# INS_CAN.net
KiCad netlist of a schematic drawn in Altium Designer
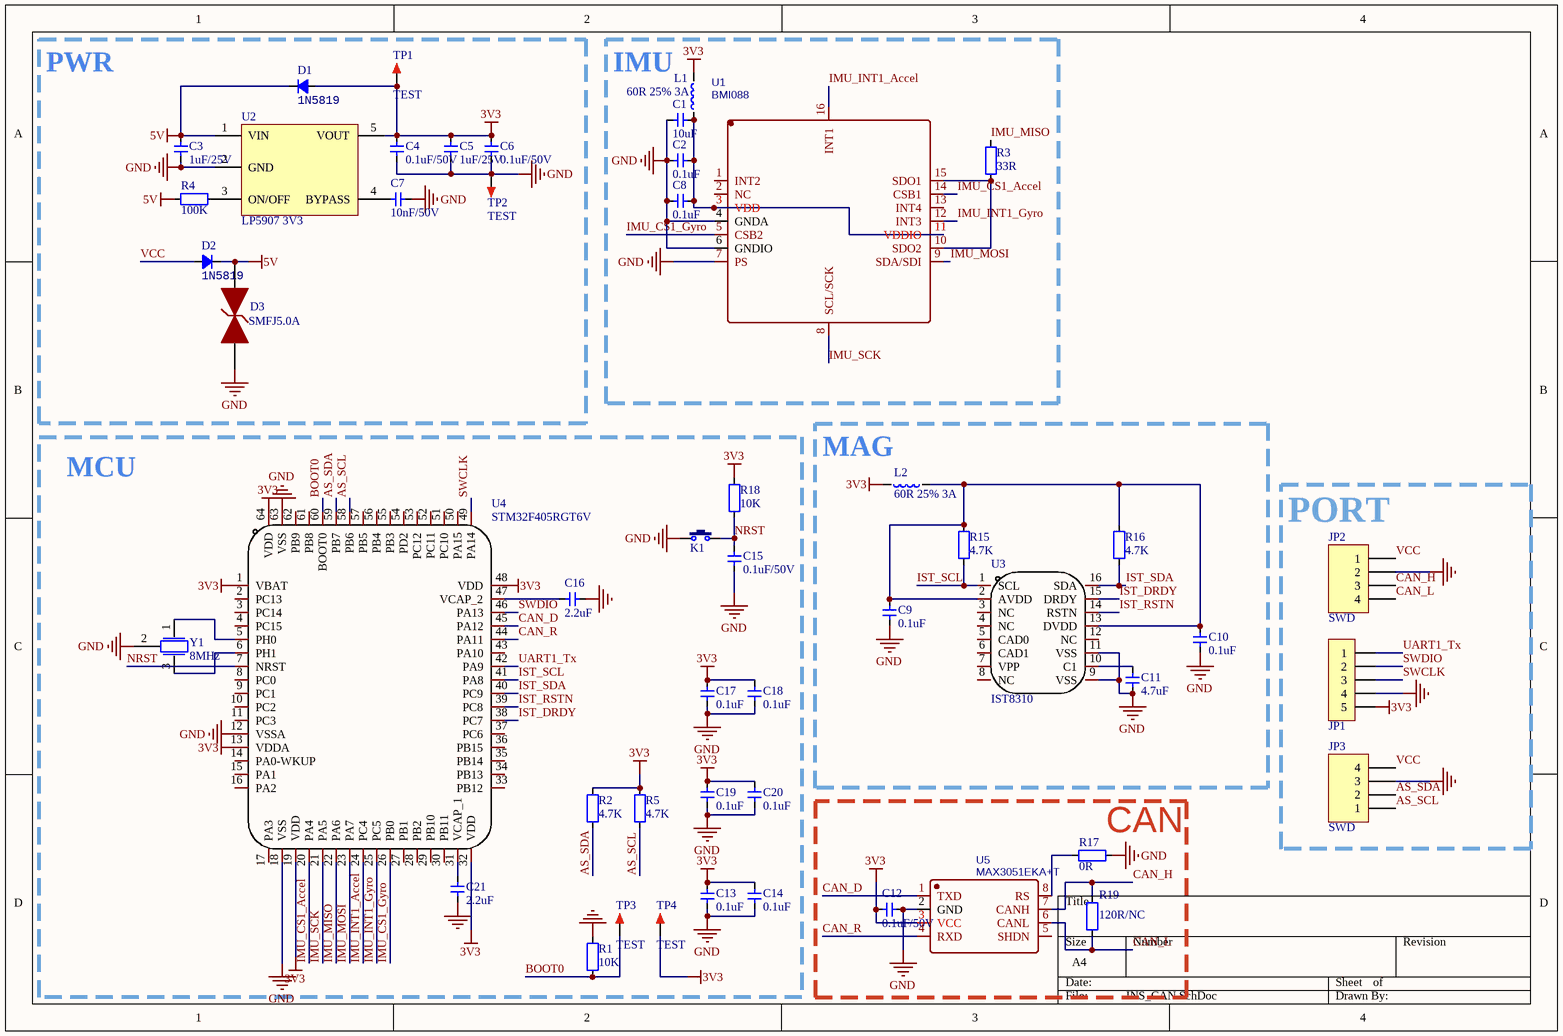
[diagram p0: INS_CAN.SchDoc]

(export (version "E")
  (design (tool "Eeschema 10.0.6"))
  (components
    (comp (ref "C1")
      (value "10uF")
      (footprint "C0402")
      (description "Capacitor")
      (libsource (lib "MyPcbLib") (part "电容-0402"))
    )
    (comp (ref "C2")
      (value "0.1uF")
      (footprint "C0402")
      (description "Capacitor")
      (libsource (lib "MyPcbLib") (part "电容-0402"))
    )
    (comp (ref "C3")
      (value "1uF/25V")
      (footprint "C0402")
      (description "Capacitor")
      (libsource (lib "MyPcbLib") (part "电容-0402"))
    )
    (comp (ref "C4")
      (value "0.1uF/50V")
      (footprint "C0402")
      (description "Capacitor")
      (libsource (lib "MyPcbLib") (part "电容-0402"))
    )
    (comp (ref "C5")
      (value "1uF/25V")
      (footprint "C0402")
      (description "Capacitor")
      (libsource (lib "MyPcbLib") (part "电容-0402"))
    )
    (comp (ref "C6")
      (value "0.1uF/50V")
      (footprint "C0402")
      (description "Capacitor")
      (libsource (lib "MyPcbLib") (part "电容-0402"))
    )
    (comp (ref "C7")
      (value "10nF/50V")
      (footprint "C0402")
      (description "Capacitor")
      (libsource (lib "MyPcbLib") (part "电容-0402"))
    )
    (comp (ref "C8")
      (value "0.1uF")
      (footprint "C0402")
      (description "Capacitor")
      (libsource (lib "MyPcbLib") (part "电容-0402"))
    )
    (comp (ref "C9")
      (value "0.1uF")
      (footprint "C0402")
      (description "Capacitor")
      (libsource (lib "MyPcbLib") (part "电容-0402"))
    )
    (comp (ref "C10")
      (value "0.1uF")
      (footprint "C0402")
      (description "Capacitor")
      (libsource (lib "MyPcbLib") (part "电容-0402"))
    )
    (comp (ref "C11")
      (value "4.7uF")
      (footprint "C0402")
      (description "Capacitor")
      (libsource (lib "MyPcbLib") (part "电容-0402"))
    )
    (comp (ref "C12")
      (value "0.1uF/50V")
      (footprint "C0402")
      (description "Capacitor")
      (libsource (lib "MyPcbLib") (part "电容-0402"))
    )
    (comp (ref "C13")
      (value "0.1uF")
      (footprint "C0402")
      (description "Capacitor")
      (libsource (lib "MyPcbLib") (part "电容-0402"))
    )
    (comp (ref "C14")
      (value "0.1uF")
      (footprint "C0402")
      (description "Capacitor")
      (libsource (lib "MyPcbLib") (part "电容-0402"))
    )
    (comp (ref "C15")
      (value "0.1uF/50V")
      (footprint "C0402")
      (description "Capacitor")
      (libsource (lib "MyPcbLib") (part "电容-0402"))
    )
    (comp (ref "C16")
      (value "2.2uF")
      (footprint "C0402")
      (description "Capacitor")
      (libsource (lib "MyPcbLib") (part "电容-0402"))
    )
    (comp (ref "C17")
      (value "0.1uF")
      (footprint "C0402")
      (description "Capacitor")
      (libsource (lib "MyPcbLib") (part "电容-0402"))
    )
    (comp (ref "C18")
      (value "0.1uF")
      (footprint "C0402")
      (description "Capacitor")
      (libsource (lib "MyPcbLib") (part "电容-0402"))
    )
    (comp (ref "C19")
      (value "0.1uF")
      (footprint "C0402")
      (description "Capacitor")
      (libsource (lib "MyPcbLib") (part "电容-0402"))
    )
    (comp (ref "C20")
      (value "0.1uF")
      (footprint "C0402")
      (description "Capacitor")
      (libsource (lib "MyPcbLib") (part "电容-0402"))
    )
    (comp (ref "C21")
      (value "2.2uF")
      (footprint "C0402")
      (description "Capacitor")
      (libsource (lib "MyPcbLib") (part "电容-0402"))
    )
    (comp (ref "D1")
      (value "1N5819")
      (footprint "D_SOD323")
      (description "Diode")
      (libsource (lib "KitSprout") (part "Diode_SMA"))
    )
    (comp (ref "D2")
      (value "1N5819")
      (footprint "D_SOD323")
      (description "Diode")
      (libsource (lib "KitSprout") (part "Diode_SMA"))
    )
    (comp (ref "D3")
      (value "SMFJ5.0A")
      (footprint "D_SOD123A")
      (libsource (lib "MyPcbLib") (part "SMBJ28CA"))
    )
    (comp (ref "JP1")
      (value "HDR-1X5")
      (footprint "MX 1.25-WS-5P")
      (description "5P接插件")
      (fields (field (name "版权归属") "源创客"))
      (libsource (lib "4.2   - 接插件-脚距1.25") (part "Header 5"))
    )
    (comp (ref "JP2")
      (value "SWD")
      (footprint "GH1.25-WS-4P")
      (libsource (lib "Schlib1") (part "Header 1*4"))
    )
    (comp (ref "JP3") (value "SWD") (footprint "GH1.25-WS-4P") (libsource (lib "") (part "Header 1*4_1")))
    (comp (ref "K1")
      (value "6x6x5")
      (footprint "SWPBS_SPST_3X2X1")
      (description "侧按直插6x6轻触开关")
      (fields (field (name "版权归属") "源创客"))
      (libsource (lib "5.1   - 按键-开关") (part "TSW DIP-6x6_V"))
    )
    (comp (ref "L1")
      (value "60R 25% 3A")
      (footprint "R0402")
      (description "小功率贴片电感")
      (fields (field (name "版权归属") "源创客"))
      (libsource (lib "3.1   - 电阻-电容-电感") (part "L"))
    )
    (comp (ref "L2")
      (value "60R 25% 3A")
      (footprint "R0402")
      (description "小功率贴片电感")
      (fields (field (name "版权归属") "源创客"))
      (libsource (lib "3.1   - 电阻-电容-电感") (part "L"))
    )
    (comp (ref "R1")
      (value "10K")
      (footprint "R0402")
      (description "Resistor")
      (libsource (lib "MyPcbLib") (part "电阻-0402"))
    )
    (comp (ref "R2")
      (value "4.7K")
      (footprint "R0402")
      (description "Resistor")
      (libsource (lib "MyPcbLib") (part "电阻-0402"))
    )
    (comp (ref "R3")
      (value "33R")
      (footprint "R0402")
      (description "Resistor")
      (libsource (lib "MyPcbLib") (part "电阻-0402"))
    )
    (comp (ref "R4")
      (value "100K")
      (footprint "R0402")
      (description "Resistor")
      (libsource (lib "") (part "电阻-0402_1"))
    )
    (comp (ref "R5")
      (value "4.7K")
      (footprint "R0402")
      (description "Resistor")
      (libsource (lib "MyPcbLib") (part "电阻-0402"))
    )
    (comp (ref "R15")
      (value "4.7K")
      (footprint "R0402")
      (description "Resistor")
      (libsource (lib "MyPcbLib") (part "电阻-0402"))
    )
    (comp (ref "R16")
      (value "4.7K")
      (footprint "R0402")
      (description "Resistor")
      (libsource (lib "MyPcbLib") (part "电阻-0402"))
    )
    (comp (ref "R17")
      (value "0R")
      (footprint "R0402")
      (description "Resistor")
      (libsource (lib "") (part "电阻-0402_2"))
    )
    (comp (ref "R18")
      (value "10K")
      (footprint "R0402")
      (description "Resistor")
      (libsource (lib "MyPcbLib") (part "电阻-0402"))
    )
    (comp (ref "R19")
      (value "120R/NC")
      (footprint "R0402")
      (description "Resistor")
      (libsource (lib "") (part "电阻-0402_3"))
    )
    (comp (ref "TP1")
      (value "TEST")
      (footprint "TEST 1")
      (description "测试点")
      (fields (field (name "版权归属") "源创客"))
      (libsource (lib "15.1 - 未分类器件") (part "TEST"))
    )
    (comp (ref "TP2")
      (value "TEST")
      (footprint "TEST 1")
      (description "测试点")
      (fields (field (name "版权归属") "源创客"))
      (libsource (lib "15.1 - 未分类器件") (part "TEST"))
    )
    (comp (ref "TP3")
      (value "TEST")
      (footprint "TEST 1")
      (description "测试点")
      (fields (field (name "版权归属") "源创客"))
      (libsource (lib "15.1 - 未分类器件") (part "TEST"))
    )
    (comp (ref "TP4")
      (value "TEST")
      (footprint "TEST 1")
      (description "测试点")
      (fields (field (name "版权归属") "源创客"))
      (libsource (lib "15.1 - 未分类器件") (part "TEST"))
    )
    (comp (ref "U1")
      (value "BMI088")
      (footprint "QFN16 BMI")
      (fields (field (name "BOM_SUPPLIER PART") "C194919") (field (name "CONTRIBUTOR") "LCSC"))
      (libsource (lib "altium-import") (part "root_0_BMI088_"))
    )
    (comp (ref "U2")
      (value "LP5907 3V3")
      (footprint "SOT23-5L")
      (description "LDO")
      (libsource (lib "MyPcbLib") (part "LP2992"))
    )
    (comp (ref "U3")
      (value "IST8310")
      (footprint "QFN50_16T_3X3_IST")
      (fields (field (name "NAME") "IST8310"))
      (libsource (lib "altium-import") (part "root_0_IST8310_"))
    )
    (comp (ref "U4")
      (value "STM32F405RGT6V")
      (footprint "LQFP64 10x10_L")
      (fields (field (name "NAME") "STM32F405RGT6V") (field (name "MANUFACTURER") "ST(意法半导体)"))
      (libsource (lib "altium-import") (part "root_0_STM32F405RGT6V_"))
    )
    (comp (ref "U5")
      (value "MAX3051EKA+T")
      (footprint "SOT23-8L")
      (fields (field (name "BOM_SUPPLIER PART") "C112005"))
      (libsource (lib "altium-import") (part "root_0_MAX3051EKA+T_"))
    )
    (comp (ref "Y1")
      (value "8MHz")
      (footprint "CSTCE3213")
      (description "村田贴片")
      (libsource (lib "MyPcbLib") (part "晶振-3Pin"))
    )
  )
  (nets
    (net (code "1") (name "/AS_SCL") (class "Default")
      (node (ref "JP3") (pin "1") (pinfunction "1_1") (pintype "passive"))
      (node (ref "R5") (pin "1") (pinfunction "1_1") (pintype "passive"))
      (node (ref "U4") (pin "58") (pinfunction "PB6_58") (pintype "passive"))
    )
    (net (code "2") (name "/AS_SDA") (class "Default")
      (node (ref "JP3") (pin "2") (pinfunction "2_2") (pintype "passive"))
      (node (ref "R2") (pin "1") (pinfunction "1_1") (pintype "passive"))
      (node (ref "U4") (pin "59") (pinfunction "PB7_59") (pintype "passive"))
    )
    (net (code "3") (name "/BOOT0") (class "Default")
      (node (ref "R1") (pin "1") (pinfunction "1_1") (pintype "passive"))
      (node (ref "TP3") (pin "1") (pinfunction "1_1") (pintype "passive"))
      (node (ref "U4") (pin "60") (pinfunction "BOOT0_60") (pintype "passive"))
    )
    (net (code "4") (name "/CAN_D") (class "Default")
      (node (ref "U4") (pin "45") (pinfunction "PA12_45") (pintype "passive"))
      (node (ref "U5") (pin "1") (pinfunction "TXD_1") (pintype "passive"))
    )
    (net (code "5") (name "/CAN_H") (class "Default")
      (node (ref "JP2") (pin "3") (pinfunction "3_3") (pintype "passive"))
      (node (ref "R19") (pin "1") (pinfunction "1_1") (pintype "passive"))
      (node (ref "U5") (pin "7") (pinfunction "CANH_7") (pintype "passive"))
    )
    (net (code "6") (name "/CAN_L") (class "Default")
      (node (ref "JP2") (pin "4") (pinfunction "4_4") (pintype "passive"))
      (node (ref "R19") (pin "2") (pinfunction "2_2") (pintype "passive"))
      (node (ref "U5") (pin "6") (pinfunction "CANL_6") (pintype "passive"))
    )
    (net (code "7") (name "/CAN_R") (class "Default")
      (node (ref "U4") (pin "44") (pinfunction "PA11_44") (pintype "passive"))
      (node (ref "U5") (pin "4") (pinfunction "RXD_4") (pintype "passive"))
    )
    (net (code "8") (name "/IMU_CS1_Accel") (class "Default")
      (node (ref "U1") (pin "14") (pinfunction "CSB1_14") (pintype "passive"))
      (node (ref "U4") (pin "20") (pinfunction "PA4_20") (pintype "passive"))
    )
    (net (code "9") (name "/IMU_CS1_Gyro") (class "Default")
      (node (ref "U1") (pin "5") (pinfunction "CSB2_5") (pintype "passive"))
      (node (ref "U4") (pin "26") (pinfunction "PB0_26") (pintype "passive"))
    )
    (net (code "10") (name "/IMU_INT1_Accel") (class "Default")
      (node (ref "U1") (pin "16") (pinfunction "INT1_16") (pintype "passive"))
      (node (ref "U4") (pin "24") (pinfunction "PC4_24") (pintype "passive"))
    )
    (net (code "11") (name "/IMU_INT1_Gyro") (class "Default")
      (node (ref "U1") (pin "12") (pinfunction "INT3_12") (pintype "passive"))
      (node (ref "U4") (pin "25") (pinfunction "PC5_25") (pintype "passive"))
    )
    (net (code "12") (name "/IMU_MISO") (class "Default")
      (node (ref "R3") (pin "2") (pinfunction "2_2") (pintype "passive"))
      (node (ref "U4") (pin "22") (pinfunction "PA6_22") (pintype "passive"))
    )
    (net (code "13") (name "/IMU_MOSI") (class "Default")
      (node (ref "U1") (pin "9") (pinfunction "SDA/SDI_9") (pintype "passive"))
      (node (ref "U4") (pin "23") (pinfunction "PA7_23") (pintype "passive"))
    )
    (net (code "14") (name "/IMU_SCK") (class "Default")
      (node (ref "U1") (pin "8") (pinfunction "SCL/SCK_8") (pintype "passive"))
      (node (ref "U4") (pin "21") (pinfunction "PA5_21") (pintype "passive"))
    )
    (net (code "15") (name "/IST_DRDY") (class "Default")
      (node (ref "U3") (pin "15") (pinfunction "DRDY_15") (pintype "passive"))
      (node (ref "U4") (pin "38") (pinfunction "PC7_38") (pintype "passive"))
    )
    (net (code "16") (name "/IST_RSTN") (class "Default")
      (node (ref "U3") (pin "14") (pinfunction "RSTN_14") (pintype "passive"))
      (node (ref "U4") (pin "39") (pinfunction "PC8_39") (pintype "passive"))
    )
    (net (code "17") (name "/IST_SCL") (class "Default")
      (node (ref "R15") (pin "1") (pinfunction "1_1") (pintype "passive"))
      (node (ref "U3") (pin "1") (pinfunction "SCL_1") (pintype "passive"))
      (node (ref "U4") (pin "41") (pinfunction "PA8_41") (pintype "passive"))
    )
    (net (code "18") (name "/IST_SDA") (class "Default")
      (node (ref "R16") (pin "1") (pinfunction "1_1") (pintype "passive"))
      (node (ref "U3") (pin "16") (pinfunction "SDA_16") (pintype "passive"))
      (node (ref "U4") (pin "40") (pinfunction "PC9_40") (pintype "passive"))
    )
    (net (code "19") (name "/NRST") (class "Default")
      (node (ref "C15") (pin "2") (pinfunction "2_2") (pintype "passive"))
      (node (ref "K1") (pin "2") (pinfunction "2_2") (pintype "passive"))
      (node (ref "R18") (pin "1") (pinfunction "1_1") (pintype "passive"))
      (node (ref "U4") (pin "7") (pinfunction "NRST_7") (pintype "passive"))
    )
    (net (code "20") (name "/SWCLK") (class "Default")
      (node (ref "JP1") (pin "3") (pinfunction "3_3") (pintype "passive"))
      (node (ref "U4") (pin "49") (pinfunction "PA14_49") (pintype "passive"))
    )
    (net (code "21") (name "/SWDIO") (class "Default")
      (node (ref "JP1") (pin "2") (pinfunction "2_2") (pintype "passive"))
      (node (ref "U4") (pin "46") (pinfunction "PA13_46") (pintype "passive"))
    )
    (net (code "22") (name "/UART1_Tx") (class "Default")
      (node (ref "JP1") (pin "1") (pinfunction "1_1") (pintype "passive"))
      (node (ref "U4") (pin "42") (pinfunction "PA9_42") (pintype "passive"))
    )
    (net (code "23") (name "/VCC") (class "Default")
      (node (ref "D2") (pin "1") (pinfunction "A_1") (pintype "passive"))
      (node (ref "JP2") (pin "1") (pinfunction "1_1") (pintype "passive"))
      (node (ref "JP3") (pin "4") (pinfunction "4_4") (pintype "passive"))
    )
    (net (code "24") (name "3V3") (class "Default")
      (node (ref "C12") (pin "2") (pinfunction "2_2") (pintype "passive"))
      (node (ref "C13") (pin "1") (pinfunction "1_1") (pintype "passive"))
      (node (ref "C14") (pin "1") (pinfunction "1_1") (pintype "passive"))
      (node (ref "C17") (pin "1") (pinfunction "1_1") (pintype "passive"))
      (node (ref "C18") (pin "1") (pinfunction "1_1") (pintype "passive"))
      (node (ref "C19") (pin "1") (pinfunction "1_1") (pintype "passive"))
      (node (ref "C20") (pin "1") (pinfunction "1_1") (pintype "passive"))
      (node (ref "C4") (pin "2") (pinfunction "2_2") (pintype "passive"))
      (node (ref "C5") (pin "2") (pinfunction "2_2") (pintype "passive"))
      (node (ref "C6") (pin "2") (pinfunction "2_2") (pintype "passive"))
      (node (ref "D1") (pin "1") (pinfunction "A_1") (pintype "passive"))
      (node (ref "JP1") (pin "5") (pinfunction "5_5") (pintype "passive"))
      (node (ref "L1") (pin "2") (pinfunction "2_2") (pintype "passive"))
      (node (ref "L2") (pin "2") (pinfunction "2_2") (pintype "passive"))
      (node (ref "R18") (pin "2") (pinfunction "2_2") (pintype "passive"))
      (node (ref "R2") (pin "2") (pinfunction "2_2") (pintype "passive"))
      (node (ref "R5") (pin "2") (pinfunction "2_2") (pintype "passive"))
      (node (ref "TP1") (pin "1") (pinfunction "1_1") (pintype "passive"))
      (node (ref "TP4") (pin "1") (pinfunction "1_1") (pintype "passive"))
      (node (ref "U2") (pin "5") (pinfunction "VOUT_5") (pintype "passive"))
      (node (ref "U4") (pin "1") (pinfunction "VBAT_1") (pintype "passive"))
      (node (ref "U4") (pin "13") (pinfunction "VDDA_13") (pintype "passive"))
      (node (ref "U4") (pin "19") (pinfunction "VDD_19") (pintype "passive"))
      (node (ref "U4") (pin "32") (pinfunction "VDD_32") (pintype "passive"))
      (node (ref "U4") (pin "48") (pinfunction "VDD_48") (pintype "passive"))
      (node (ref "U4") (pin "64") (pinfunction "VDD_64") (pintype "passive"))
      (node (ref "U5") (pin "3") (pinfunction "VCC_3") (pintype "passive"))
    )
    (net (code "25") (name "5V") (class "Default")
      (node (ref "C3") (pin "2") (pinfunction "2_2") (pintype "passive"))
      (node (ref "D1") (pin "2") (pinfunction "K_2") (pintype "passive"))
      (node (ref "D2") (pin "2") (pinfunction "K_2") (pintype "passive"))
      (node (ref "D3") (pin "2") (pinfunction "2_2") (pintype "passive"))
      (node (ref "R4") (pin "1") (pinfunction "1_1") (pintype "passive"))
      (node (ref "U2") (pin "1") (pinfunction "VIN_1") (pintype "passive"))
    )
    (net (code "26") (name "GND") (class "Default")
      (node (ref "C1") (pin "2") (pinfunction "2_2") (pintype "passive"))
      (node (ref "C10") (pin "2") (pinfunction "2_2") (pintype "passive"))
      (node (ref "C11") (pin "2") (pinfunction "2_2") (pintype "passive"))
      (node (ref "C12") (pin "1") (pinfunction "1_1") (pintype "passive"))
      (node (ref "C13") (pin "2") (pinfunction "2_2") (pintype "passive"))
      (node (ref "C14") (pin "2") (pinfunction "2_2") (pintype "passive"))
      (node (ref "C15") (pin "1") (pinfunction "1_1") (pintype "passive"))
      (node (ref "C16") (pin "2") (pinfunction "2_2") (pintype "passive"))
      (node (ref "C17") (pin "2") (pinfunction "2_2") (pintype "passive"))
      (node (ref "C18") (pin "2") (pinfunction "2_2") (pintype "passive"))
      (node (ref "C19") (pin "2") (pinfunction "2_2") (pintype "passive"))
      (node (ref "C2") (pin "2") (pinfunction "2_2") (pintype "passive"))
      (node (ref "C20") (pin "2") (pinfunction "2_2") (pintype "passive"))
      (node (ref "C21") (pin "2") (pinfunction "2_2") (pintype "passive"))
      (node (ref "C3") (pin "1") (pinfunction "1_1") (pintype "passive"))
      (node (ref "C4") (pin "1") (pinfunction "1_1") (pintype "passive"))
      (node (ref "C5") (pin "1") (pinfunction "1_1") (pintype "passive"))
      (node (ref "C6") (pin "1") (pinfunction "1_1") (pintype "passive"))
      (node (ref "C7") (pin "1") (pinfunction "1_1") (pintype "passive"))
      (node (ref "C8") (pin "2") (pinfunction "2_2") (pintype "passive"))
      (node (ref "C9") (pin "2") (pinfunction "2_2") (pintype "passive"))
      (node (ref "D3") (pin "1") (pinfunction "1_1") (pintype "passive"))
      (node (ref "JP1") (pin "4") (pinfunction "4_4") (pintype "passive"))
      (node (ref "JP2") (pin "2") (pinfunction "2_2") (pintype "passive"))
      (node (ref "JP3") (pin "3") (pinfunction "3_3") (pintype "passive"))
      (node (ref "K1") (pin "1") (pinfunction "1_1") (pintype "passive"))
      (node (ref "R1") (pin "2") (pinfunction "2_2") (pintype "passive"))
      (node (ref "R17") (pin "1") (pinfunction "1_1") (pintype "passive"))
      (node (ref "TP2") (pin "1") (pinfunction "1_1") (pintype "passive"))
      (node (ref "U1") (pin "4") (pinfunction "GNDA_4") (pintype "passive"))
      (node (ref "U1") (pin "6") (pinfunction "GNDIO_6") (pintype "passive"))
      (node (ref "U1") (pin "7") (pinfunction "PS_7") (pintype "passive"))
      (node (ref "U2") (pin "2") (pinfunction "GND_2") (pintype "passive"))
      (node (ref "U3") (pin "11") (pinfunction "VSS_11") (pintype "passive"))
      (node (ref "U3") (pin "9") (pinfunction "VSS_9") (pintype "passive"))
      (node (ref "U4") (pin "12") (pinfunction "VSSA_12") (pintype "passive"))
      (node (ref "U4") (pin "18") (pinfunction "VSS_18") (pintype "passive"))
      (node (ref "U4") (pin "63") (pinfunction "VSS_63") (pintype "passive"))
      (node (ref "U5") (pin "2") (pinfunction "GND_2") (pintype "passive"))
      (node (ref "Y1") (pin "2") (pinfunction "2_2") (pintype "passive"))
    )
    (net (code "27") (name "Net-(U1-SDO1)") (class "Default")
      (node (ref "R3") (pin "1") (pinfunction "1_1") (pintype "passive"))
      (node (ref "U1") (pin "10") (pinfunction "SDO2_10") (pintype "passive"))
      (node (ref "U1") (pin "15") (pinfunction "SDO1_15") (pintype "passive"))
    )
    (net (code "28") (name "Net-(U1-VDD)") (class "Default")
      (node (ref "C1") (pin "1") (pinfunction "1_1") (pintype "passive"))
      (node (ref "C2") (pin "1") (pinfunction "1_1") (pintype "passive"))
      (node (ref "C8") (pin "1") (pinfunction "1_1") (pintype "passive"))
      (node (ref "L1") (pin "1") (pinfunction "1_1") (pintype "passive"))
      (node (ref "U1") (pin "11") (pinfunction "VDDIO_11") (pintype "passive"))
      (node (ref "U1") (pin "3") (pinfunction "VDD_3") (pintype "passive"))
    )
    (net (code "29") (name "Net-(U2-BYPASS)") (class "Default")
      (node (ref "C7") (pin "2") (pinfunction "2_2") (pintype "passive"))
      (node (ref "U2") (pin "4") (pinfunction "BYPASS_4") (pintype "passive"))
    )
    (net (code "30") (name "Net-(U2-ON{slash}OFF)") (class "Default")
      (node (ref "R4") (pin "2") (pinfunction "2_2") (pintype "passive"))
      (node (ref "U2") (pin "3") (pinfunction "ON/OFF_3") (pintype "passive"))
    )
    (net (code "31") (name "Net-(U3-AVDD)") (class "Default")
      (node (ref "C10") (pin "1") (pinfunction "1_1") (pintype "passive"))
      (node (ref "C9") (pin "1") (pinfunction "1_1") (pintype "passive"))
      (node (ref "L2") (pin "1") (pinfunction "1_1") (pintype "passive"))
      (node (ref "R15") (pin "2") (pinfunction "2_2") (pintype "passive"))
      (node (ref "R16") (pin "2") (pinfunction "2_2") (pintype "passive"))
      (node (ref "U3") (pin "13") (pinfunction "DVDD_13") (pintype "passive"))
      (node (ref "U3") (pin "2") (pinfunction "AVDD_2") (pintype "passive"))
    )
    (net (code "32") (name "Net-(U3-C1)") (class "Default")
      (node (ref "C11") (pin "1") (pinfunction "1_1") (pintype "passive"))
      (node (ref "U3") (pin "10") (pinfunction "C1_10") (pintype "passive"))
    )
    (net (code "33") (name "Net-(U4-PH0)") (class "Default")
      (node (ref "U4") (pin "5") (pinfunction "PH0_5") (pintype "passive"))
      (node (ref "Y1") (pin "1") (pinfunction "1_1") (pintype "passive"))
    )
    (net (code "34") (name "Net-(U4-PH1)") (class "Default")
      (node (ref "U4") (pin "6") (pinfunction "PH1_6") (pintype "passive"))
      (node (ref "Y1") (pin "3") (pinfunction "3_3") (pintype "passive"))
    )
    (net (code "35") (name "Net-(U4-VCAP_1)") (class "Default")
      (node (ref "C21") (pin "1") (pinfunction "1_1") (pintype "passive"))
      (node (ref "U4") (pin "31") (pinfunction "VCAP_1_31") (pintype "passive"))
    )
    (net (code "36") (name "Net-(U4-VCAP_2)") (class "Default")
      (node (ref "C16") (pin "1") (pinfunction "1_1") (pintype "passive"))
      (node (ref "U4") (pin "47") (pinfunction "VCAP_2_47") (pintype "passive"))
    )
    (net (code "37") (name "Net-(U5-RS)") (class "Default")
      (node (ref "R17") (pin "2") (pinfunction "2_2") (pintype "passive"))
      (node (ref "U5") (pin "8") (pinfunction "RS_8") (pintype "passive"))
    )
    (net (code "38") (name "unconnected-(U1-INT2-Pad1)") (class "Default")
      (node (ref "U1") (pin "1") (pinfunction "INT2_1") (pintype "passive"))
    )
    (net (code "39") (name "unconnected-(U1-INT4-Pad13)") (class "Default")
      (node (ref "U1") (pin "13") (pinfunction "INT4_13") (pintype "passive"))
    )
    (net (code "40") (name "unconnected-(U1-NC-Pad2)") (class "Default")
      (node (ref "U1") (pin "2") (pinfunction "NC_2") (pintype "passive"))
    )
    (net (code "41") (name "unconnected-(U3-CAD0-Pad5)") (class "Default")
      (node (ref "U3") (pin "5") (pinfunction "CAD0_5") (pintype "passive"))
    )
    (net (code "42") (name "unconnected-(U3-CAD1-Pad6)") (class "Default")
      (node (ref "U3") (pin "6") (pinfunction "CAD1_6") (pintype "passive"))
    )
    (net (code "43") (name "unconnected-(U3-NC-Pad3)") (class "Default")
      (node (ref "U3") (pin "3") (pinfunction "NC_3") (pintype "passive"))
    )
    (net (code "44") (name "unconnected-(U3-NC-Pad4)") (class "Default")
      (node (ref "U3") (pin "4") (pinfunction "NC_4") (pintype "passive"))
    )
    (net (code "45") (name "unconnected-(U3-NC-Pad8)") (class "Default")
      (node (ref "U3") (pin "8") (pinfunction "NC_8") (pintype "passive"))
    )
    (net (code "46") (name "unconnected-(U3-NC-Pad12)") (class "Default")
      (node (ref "U3") (pin "12") (pinfunction "NC_12") (pintype "passive"))
    )
    (net (code "47") (name "unconnected-(U3-VPP-Pad7)") (class "Default")
      (node (ref "U3") (pin "7") (pinfunction "VPP_7") (pintype "passive"))
    )
    (net (code "48") (name "unconnected-(U4-PA0-WKUP-Pad14)") (class "Default")
      (node (ref "U4") (pin "14") (pinfunction "PA0-WKUP_14") (pintype "passive"))
    )
    (net (code "49") (name "unconnected-(U4-PA1-Pad15)") (class "Default")
      (node (ref "U4") (pin "15") (pinfunction "PA1_15") (pintype "passive"))
    )
    (net (code "50") (name "unconnected-(U4-PA2-Pad16)") (class "Default")
      (node (ref "U4") (pin "16") (pinfunction "PA2_16") (pintype "passive"))
    )
    (net (code "51") (name "unconnected-(U4-PA3-Pad17)") (class "Default")
      (node (ref "U4") (pin "17") (pinfunction "PA3_17") (pintype "passive"))
    )
    (net (code "52") (name "unconnected-(U4-PA10-Pad43)") (class "Default")
      (node (ref "U4") (pin "43") (pinfunction "PA10_43") (pintype "passive"))
    )
    (net (code "53") (name "unconnected-(U4-PA15-Pad50)") (class "Default")
      (node (ref "U4") (pin "50") (pinfunction "PA15_50") (pintype "passive"))
    )
    (net (code "54") (name "unconnected-(U4-PB1-Pad27)") (class "Default")
      (node (ref "U4") (pin "27") (pinfunction "PB1_27") (pintype "passive"))
    )
    (net (code "55") (name "unconnected-(U4-PB2-Pad28)") (class "Default")
      (node (ref "U4") (pin "28") (pinfunction "PB2_28") (pintype "passive"))
    )
    (net (code "56") (name "unconnected-(U4-PB3-Pad55)") (class "Default")
      (node (ref "U4") (pin "55") (pinfunction "PB3_55") (pintype "passive"))
    )
    (net (code "57") (name "unconnected-(U4-PB4-Pad56)") (class "Default")
      (node (ref "U4") (pin "56") (pinfunction "PB4_56") (pintype "passive"))
    )
    (net (code "58") (name "unconnected-(U4-PB5-Pad57)") (class "Default")
      (node (ref "U4") (pin "57") (pinfunction "PB5_57") (pintype "passive"))
    )
    (net (code "59") (name "unconnected-(U4-PB8-Pad61)") (class "Default")
      (node (ref "U4") (pin "61") (pinfunction "PB8_61") (pintype "passive"))
    )
    (net (code "60") (name "unconnected-(U4-PB9-Pad62)") (class "Default")
      (node (ref "U4") (pin "62") (pinfunction "PB9_62") (pintype "passive"))
    )
    (net (code "61") (name "unconnected-(U4-PB10-Pad29)") (class "Default")
      (node (ref "U4") (pin "29") (pinfunction "PB10_29") (pintype "passive"))
    )
    (net (code "62") (name "unconnected-(U4-PB11-Pad30)") (class "Default")
      (node (ref "U4") (pin "30") (pinfunction "PB11_30") (pintype "passive"))
    )
    (net (code "63") (name "unconnected-(U4-PB12-Pad33)") (class "Default")
      (node (ref "U4") (pin "33") (pinfunction "PB12_33") (pintype "passive"))
    )
    (net (code "64") (name "unconnected-(U4-PB13-Pad34)") (class "Default")
      (node (ref "U4") (pin "34") (pinfunction "PB13_34") (pintype "passive"))
    )
    (net (code "65") (name "unconnected-(U4-PB14-Pad35)") (class "Default")
      (node (ref "U4") (pin "35") (pinfunction "PB14_35") (pintype "passive"))
    )
    (net (code "66") (name "unconnected-(U4-PB15-Pad36)") (class "Default")
      (node (ref "U4") (pin "36") (pinfunction "PB15_36") (pintype "passive"))
    )
    (net (code "67") (name "unconnected-(U4-PC0-Pad8)") (class "Default")
      (node (ref "U4") (pin "8") (pinfunction "PC0_8") (pintype "passive"))
    )
    (net (code "68") (name "unconnected-(U4-PC1-Pad9)") (class "Default")
      (node (ref "U4") (pin "9") (pinfunction "PC1_9") (pintype "passive"))
    )
    (net (code "69") (name "unconnected-(U4-PC2-Pad10)") (class "Default")
      (node (ref "U4") (pin "10") (pinfunction "PC2_10") (pintype "passive"))
    )
    (net (code "70") (name "unconnected-(U4-PC3-Pad11)") (class "Default")
      (node (ref "U4") (pin "11") (pinfunction "PC3_11") (pintype "passive"))
    )
    (net (code "71") (name "unconnected-(U4-PC6-Pad37)") (class "Default")
      (node (ref "U4") (pin "37") (pinfunction "PC6_37") (pintype "passive"))
    )
    (net (code "72") (name "unconnected-(U4-PC10-Pad51)") (class "Default")
      (node (ref "U4") (pin "51") (pinfunction "PC10_51") (pintype "passive"))
    )
    (net (code "73") (name "unconnected-(U4-PC11-Pad52)") (class "Default")
      (node (ref "U4") (pin "52") (pinfunction "PC11_52") (pintype "passive"))
    )
    (net (code "74") (name "unconnected-(U4-PC12-Pad53)") (class "Default")
      (node (ref "U4") (pin "53") (pinfunction "PC12_53") (pintype "passive"))
    )
    (net (code "75") (name "unconnected-(U4-PC13-Pad2)") (class "Default")
      (node (ref "U4") (pin "2") (pinfunction "PC13_2") (pintype "passive"))
    )
    (net (code "76") (name "unconnected-(U4-PC14-Pad3)") (class "Default")
      (node (ref "U4") (pin "3") (pinfunction "PC14_3") (pintype "passive"))
    )
    (net (code "77") (name "unconnected-(U4-PC15-Pad4)") (class "Default")
      (node (ref "U4") (pin "4") (pinfunction "PC15_4") (pintype "passive"))
    )
    (net (code "78") (name "unconnected-(U4-PD2-Pad54)") (class "Default")
      (node (ref "U4") (pin "54") (pinfunction "PD2_54") (pintype "passive"))
    )
    (net (code "79") (name "unconnected-(U5-SHDN-Pad5)") (class "Default")
      (node (ref "U5") (pin "5") (pinfunction "SHDN_5") (pintype "passive"))
    )
  )
)
